# VL6180_2.net
KiCad netlist of a schematic drawn in EAGLE
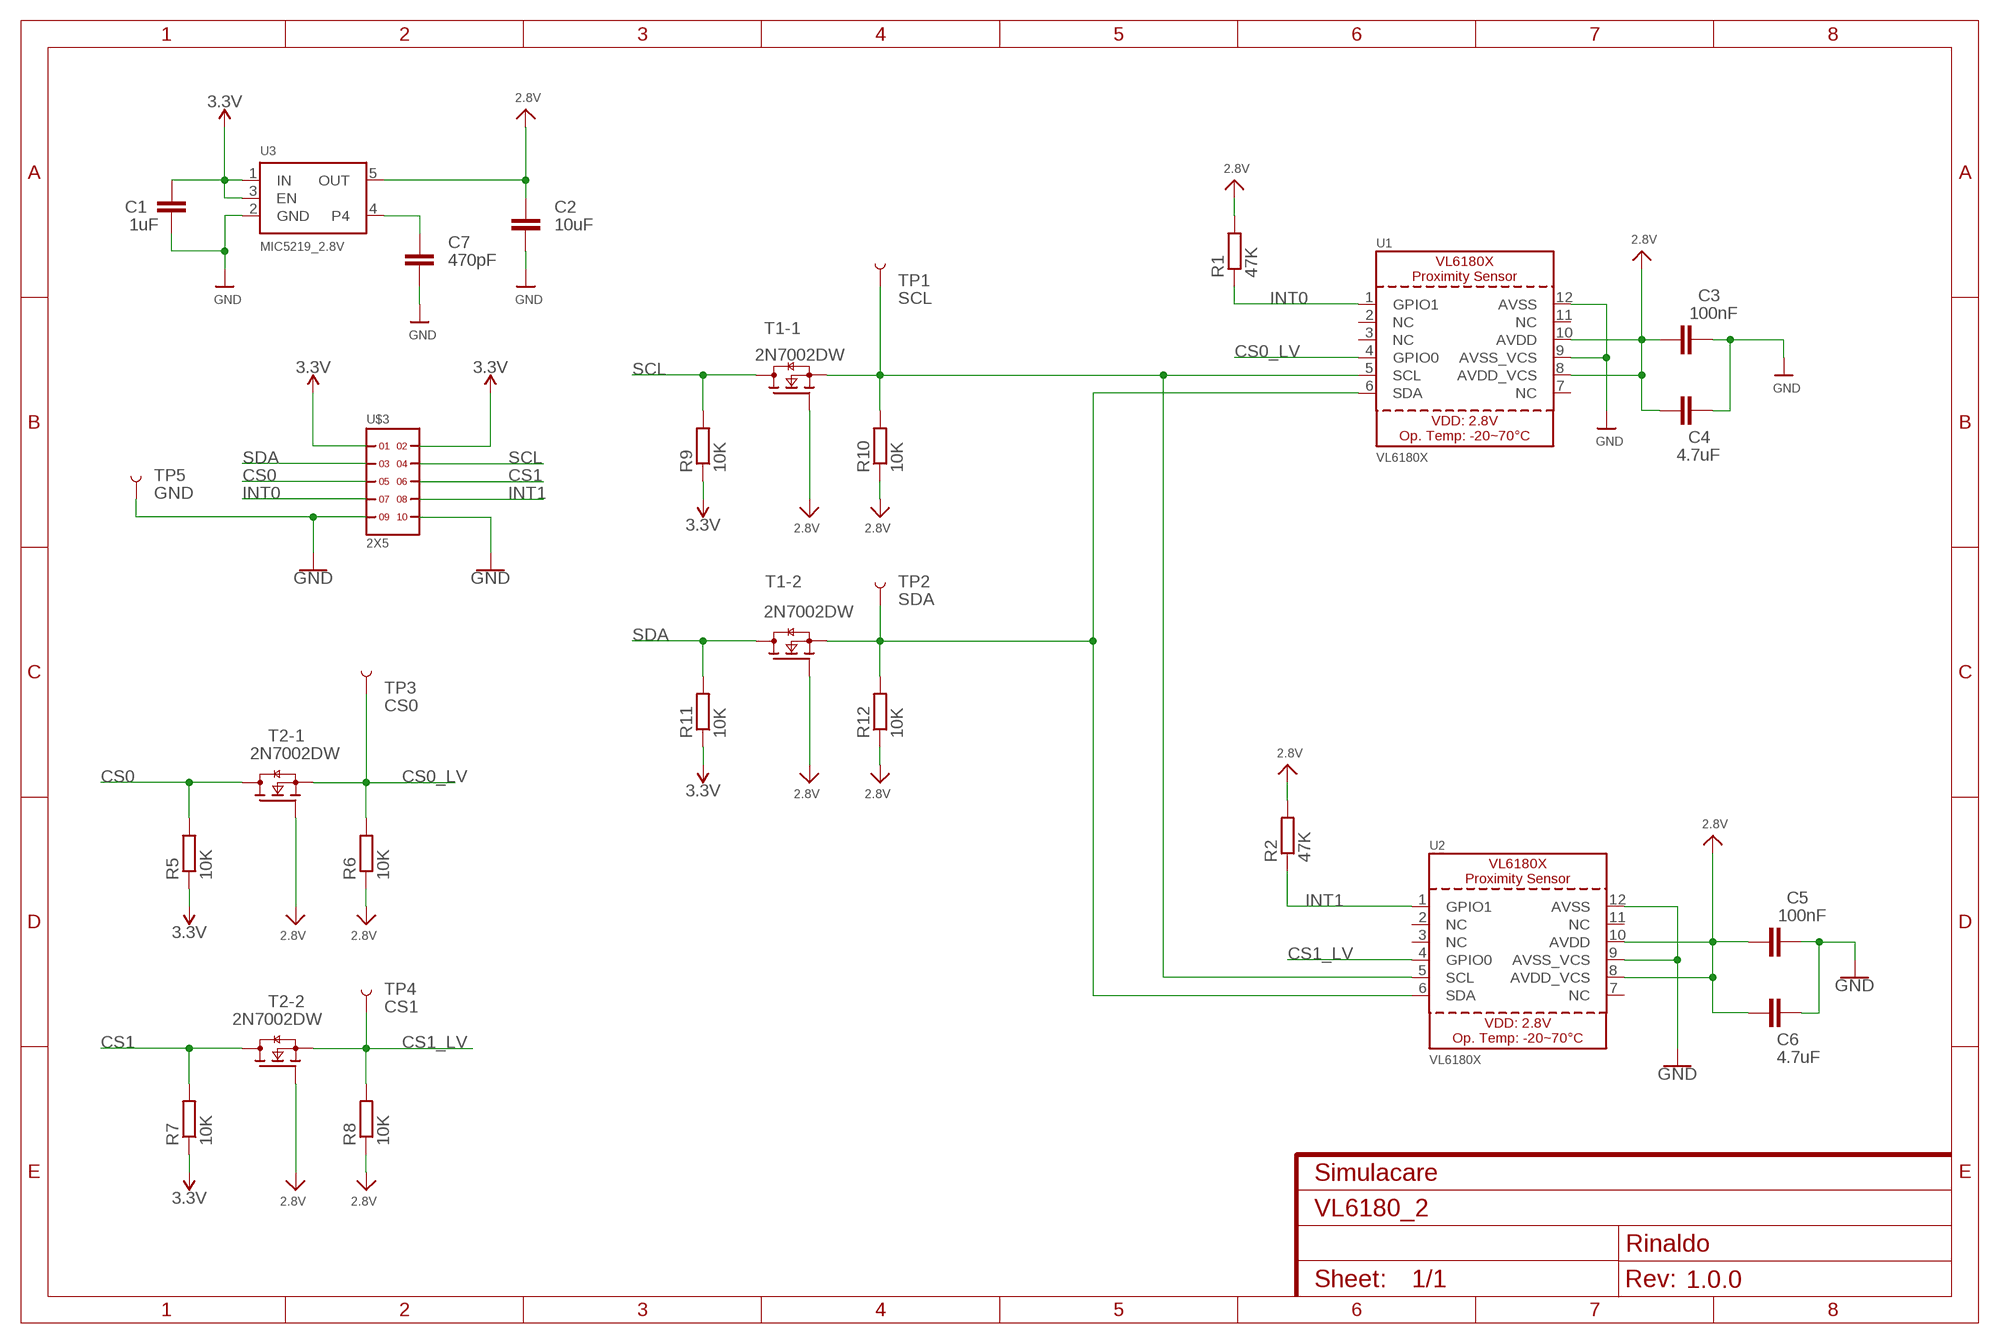
[diagram p0: schematic, sheet 1]

(export (version "E")
  (design (tool "Eeschema 10.0.6"))
  (components
    (comp (ref "C1")
      (value "1uF")
      (footprint "eagle-import:C0603")
      (libsource (lib "eagle-import") (part "C-EUC0603"))
    )
    (comp (ref "C2")
      (value "10uF")
      (footprint "eagle-import:C0603")
      (libsource (lib "eagle-import") (part "C-EUC0603"))
    )
    (comp (ref "C3")
      (value "100nF")
      (footprint "eagle-import:C0603")
      (libsource (lib "eagle-import") (part "C-EUC0603"))
    )
    (comp (ref "C4")
      (value "4.7uF")
      (footprint "eagle-import:C0603")
      (libsource (lib "eagle-import") (part "C-EUC0603"))
    )
    (comp (ref "C5")
      (value "100nF")
      (footprint "eagle-import:C0603")
      (libsource (lib "eagle-import") (part "C-EUC0603"))
    )
    (comp (ref "C6")
      (value "4.7uF")
      (footprint "eagle-import:C0603")
      (libsource (lib "eagle-import") (part "C-EUC0603"))
    )
    (comp (ref "C7")
      (value "470pF")
      (footprint "eagle-import:C0603")
      (libsource (lib "eagle-import") (part "C-EUC0603"))
    )
    (comp (ref "R1")
      (value "47K")
      (footprint "eagle-import:R0603")
      (libsource (lib "eagle-import") (part "R-EU_R0603"))
    )
    (comp (ref "R2")
      (value "47K")
      (footprint "eagle-import:R0603")
      (libsource (lib "eagle-import") (part "R-EU_R0603"))
    )
    (comp (ref "R5")
      (value "10K")
      (footprint "eagle-import:R0603")
      (libsource (lib "eagle-import") (part "R-EU_R0603"))
    )
    (comp (ref "R6")
      (value "10K")
      (footprint "eagle-import:R0603")
      (libsource (lib "eagle-import") (part "R-EU_R0603"))
    )
    (comp (ref "R7")
      (value "10K")
      (footprint "eagle-import:R0603")
      (libsource (lib "eagle-import") (part "R-EU_R0603"))
    )
    (comp (ref "R8")
      (value "10K")
      (footprint "eagle-import:R0603")
      (libsource (lib "eagle-import") (part "R-EU_R0603"))
    )
    (comp (ref "R9")
      (value "10K")
      (footprint "eagle-import:R0603")
      (libsource (lib "eagle-import") (part "R-EU_R0603"))
    )
    (comp (ref "R10")
      (value "10K")
      (footprint "eagle-import:R0603")
      (libsource (lib "eagle-import") (part "R-EU_R0603"))
    )
    (comp (ref "R11")
      (value "10K")
      (footprint "eagle-import:R0603")
      (libsource (lib "eagle-import") (part "R-EU_R0603"))
    )
    (comp (ref "R12")
      (value "10K")
      (footprint "eagle-import:R0603")
      (libsource (lib "eagle-import") (part "R-EU_R0603"))
    )
    (comp (ref "T1")
      (value "2N7002DW")
      (footprint "eagle-import:SOT363")
      (libsource (lib "eagle-import") (part "2N7002BKS"))
    )
    (comp (ref "T2")
      (value "2N7002DW")
      (footprint "eagle-import:SOT363")
      (libsource (lib "eagle-import") (part "2N7002BKS"))
    )
    (comp (ref "TP1")
      (value "SCL")
      (footprint "eagle-import:PAD.03X.04")
      (libsource (lib "eagle-import") (part "TEST-POINT3X4"))
    )
    (comp (ref "TP2")
      (value "SDA")
      (footprint "eagle-import:PAD.03X.04")
      (libsource (lib "eagle-import") (part "TEST-POINT3X4"))
    )
    (comp (ref "TP3")
      (value "CS0")
      (footprint "eagle-import:PAD.03X.04")
      (libsource (lib "eagle-import") (part "TEST-POINT3X4"))
    )
    (comp (ref "TP4")
      (value "CS1")
      (footprint "eagle-import:PAD.03X.04")
      (libsource (lib "eagle-import") (part "TEST-POINT3X4"))
    )
    (comp (ref "TP5")
      (value "GND")
      (footprint "eagle-import:PAD.03X.04")
      (libsource (lib "eagle-import") (part "TEST-POINT3X4"))
    )
    (comp (ref "U$3")
      (value "2X5")
      (footprint "eagle-import:2X5")
      (libsource (lib "eagle-import") (part "2X5"))
    )
    (comp (ref "U1")
      (value "VL6180X")
      (footprint "eagle-import:VL6180")
      (libsource (lib "eagle-import") (part "VL6180X"))
    )
    (comp (ref "U2")
      (value "VL6180X")
      (footprint "eagle-import:VL6180")
      (libsource (lib "eagle-import") (part "VL6180X"))
    )
    (comp (ref "U3")
      (value "MIC5219_2.8V")
      (footprint "eagle-import:SOT23-5")
      (libsource (lib "eagle-import") (part "VREG_SOT23-5"))
    )
  )
  (nets
    (net (code "1") (name "/CS0") (class "Default")
      (node (ref "R5") (pin "2") (pinfunction "2_2") (pintype "passive"))
      (node (ref "T2") (pin "6") (pinfunction "D_6") (pintype "passive"))
      (node (ref "U$3") (pin "5") (pinfunction "5_5") (pintype "bidirectional"))
    )
    (net (code "2") (name "/CS0_LV") (class "Default")
      (node (ref "R6") (pin "2") (pinfunction "2_2") (pintype "passive"))
      (node (ref "T2") (pin "1") (pinfunction "S_1") (pintype "passive"))
      (node (ref "TP3") (pin "P$1") (pinfunction "1_P$1") (pintype "bidirectional"))
      (node (ref "U1") (pin "4") (pinfunction "GPIO0_4") (pintype "bidirectional"))
    )
    (net (code "3") (name "/CS1") (class "Default")
      (node (ref "R7") (pin "2") (pinfunction "2_2") (pintype "passive"))
      (node (ref "T2") (pin "3") (pinfunction "D_3") (pintype "passive"))
      (node (ref "U$3") (pin "6") (pinfunction "6_6") (pintype "bidirectional"))
    )
    (net (code "4") (name "/CS1_LV") (class "Default")
      (node (ref "R8") (pin "2") (pinfunction "2_2") (pintype "passive"))
      (node (ref "T2") (pin "4") (pinfunction "S_4") (pintype "passive"))
      (node (ref "TP4") (pin "P$1") (pinfunction "1_P$1") (pintype "bidirectional"))
      (node (ref "U2") (pin "4") (pinfunction "GPIO0_4") (pintype "bidirectional"))
    )
    (net (code "5") (name "/INT0") (class "Default")
      (node (ref "R1") (pin "1") (pinfunction "1_1") (pintype "passive"))
      (node (ref "U$3") (pin "7") (pinfunction "7_7") (pintype "bidirectional"))
      (node (ref "U1") (pin "1") (pinfunction "GPIO1_1") (pintype "bidirectional"))
    )
    (net (code "6") (name "/INT1") (class "Default")
      (node (ref "R2") (pin "1") (pinfunction "1_1") (pintype "passive"))
      (node (ref "U$3") (pin "8") (pinfunction "8_8") (pintype "bidirectional"))
      (node (ref "U2") (pin "1") (pinfunction "GPIO1_1") (pintype "bidirectional"))
    )
    (net (code "7") (name "/SCL") (class "Default")
      (node (ref "R9") (pin "2") (pinfunction "2_2") (pintype "passive"))
      (node (ref "T1") (pin "6") (pinfunction "D_6") (pintype "passive"))
      (node (ref "U$3") (pin "4") (pinfunction "4_4") (pintype "bidirectional"))
    )
    (net (code "8") (name "/SDA") (class "Default")
      (node (ref "R11") (pin "2") (pinfunction "2_2") (pintype "passive"))
      (node (ref "T1") (pin "3") (pinfunction "D_3") (pintype "passive"))
      (node (ref "U$3") (pin "3") (pinfunction "3_3") (pintype "bidirectional"))
    )
    (net (code "9") (name "2.8V") (class "Default")
      (node (ref "C2") (pin "1") (pinfunction "1_1") (pintype "passive"))
      (node (ref "C3") (pin "1") (pinfunction "1_1") (pintype "passive"))
      (node (ref "C4") (pin "1") (pinfunction "1_1") (pintype "passive"))
      (node (ref "C5") (pin "1") (pinfunction "1_1") (pintype "passive"))
      (node (ref "C6") (pin "1") (pinfunction "1_1") (pintype "passive"))
      (node (ref "R1") (pin "2") (pinfunction "2_2") (pintype "passive"))
      (node (ref "R10") (pin "1") (pinfunction "1_1") (pintype "passive"))
      (node (ref "R12") (pin "1") (pinfunction "1_1") (pintype "passive"))
      (node (ref "R2") (pin "2") (pinfunction "2_2") (pintype "passive"))
      (node (ref "R6") (pin "1") (pinfunction "1_1") (pintype "passive"))
      (node (ref "R8") (pin "1") (pinfunction "1_1") (pintype "passive"))
      (node (ref "T1") (pin "2") (pinfunction "G_2") (pintype "passive"))
      (node (ref "T1") (pin "5") (pinfunction "G_5") (pintype "passive"))
      (node (ref "T2") (pin "2") (pinfunction "G_2") (pintype "passive"))
      (node (ref "T2") (pin "5") (pinfunction "G_5") (pintype "passive"))
      (node (ref "U1") (pin "10") (pinfunction "AVDD_10") (pintype "power_in"))
      (node (ref "U1") (pin "8") (pinfunction "AVDD_VCS_8") (pintype "power_in"))
      (node (ref "U2") (pin "10") (pinfunction "AVDD_10") (pintype "power_in"))
      (node (ref "U2") (pin "8") (pinfunction "AVDD_VCS_8") (pintype "power_in"))
      (node (ref "U3") (pin "5") (pinfunction "OUT_5") (pintype "power_in"))
    )
    (net (code "10") (name "3.3V") (class "Default")
      (node (ref "C1") (pin "1") (pinfunction "1_1") (pintype "passive"))
      (node (ref "R11") (pin "1") (pinfunction "1_1") (pintype "passive"))
      (node (ref "R5") (pin "1") (pinfunction "1_1") (pintype "passive"))
      (node (ref "R7") (pin "1") (pinfunction "1_1") (pintype "passive"))
      (node (ref "R9") (pin "1") (pinfunction "1_1") (pintype "passive"))
      (node (ref "U$3") (pin "1") (pinfunction "1_1") (pintype "bidirectional"))
      (node (ref "U$3") (pin "2") (pinfunction "2_2") (pintype "bidirectional"))
      (node (ref "U3") (pin "1") (pinfunction "IN_1") (pintype "power_in"))
      (node (ref "U3") (pin "3") (pinfunction "EN_3") (pintype "input"))
    )
    (net (code "11") (name "GND") (class "Default")
      (node (ref "C1") (pin "2") (pinfunction "2_2") (pintype "passive"))
      (node (ref "C2") (pin "2") (pinfunction "2_2") (pintype "passive"))
      (node (ref "C3") (pin "2") (pinfunction "2_2") (pintype "passive"))
      (node (ref "C4") (pin "2") (pinfunction "2_2") (pintype "passive"))
      (node (ref "C5") (pin "2") (pinfunction "2_2") (pintype "passive"))
      (node (ref "C6") (pin "2") (pinfunction "2_2") (pintype "passive"))
      (node (ref "C7") (pin "2") (pinfunction "2_2") (pintype "passive"))
      (node (ref "TP5") (pin "P$1") (pinfunction "1_P$1") (pintype "bidirectional"))
      (node (ref "U$3") (pin "10") (pinfunction "10_10") (pintype "bidirectional"))
      (node (ref "U$3") (pin "9") (pinfunction "9_9") (pintype "bidirectional"))
      (node (ref "U1") (pin "12") (pinfunction "AVSS_12") (pintype "power_in"))
      (node (ref "U1") (pin "9") (pinfunction "AVSS_VCS_9") (pintype "power_in"))
      (node (ref "U2") (pin "12") (pinfunction "AVSS_12") (pintype "power_in"))
      (node (ref "U2") (pin "9") (pinfunction "AVSS_VCS_9") (pintype "power_in"))
      (node (ref "U3") (pin "2") (pinfunction "GND_2") (pintype "power_in"))
    )
    (net (code "12") (name "Net-(T1A-S)") (class "Default")
      (node (ref "R10") (pin "2") (pinfunction "2_2") (pintype "passive"))
      (node (ref "T1") (pin "1") (pinfunction "S_1") (pintype "passive"))
      (node (ref "TP1") (pin "P$1") (pinfunction "1_P$1") (pintype "bidirectional"))
      (node (ref "U1") (pin "5") (pinfunction "SCL_5") (pintype "input"))
      (node (ref "U2") (pin "5") (pinfunction "SCL_5") (pintype "input"))
    )
    (net (code "13") (name "Net-(T1B-S)") (class "Default")
      (node (ref "R12") (pin "2") (pinfunction "2_2") (pintype "passive"))
      (node (ref "T1") (pin "4") (pinfunction "S_4") (pintype "passive"))
      (node (ref "TP2") (pin "P$1") (pinfunction "1_P$1") (pintype "bidirectional"))
      (node (ref "U1") (pin "6") (pinfunction "SDA_6") (pintype "bidirectional"))
      (node (ref "U2") (pin "6") (pinfunction "SDA_6") (pintype "bidirectional"))
    )
    (net (code "14") (name "Net-(U3-P4)") (class "Default")
      (node (ref "C7") (pin "1") (pinfunction "1_1") (pintype "passive"))
      (node (ref "U3") (pin "4") (pinfunction "P4_4") (pintype "bidirectional"))
    )
    (net (code "15") (name "unconnected-(U1-NC-Pad2)") (class "Default")
      (node (ref "U1") (pin "2") (pinfunction "NC_2") (pintype "no_connect"))
    )
    (net (code "16") (name "unconnected-(U1-NC-Pad3)") (class "Default")
      (node (ref "U1") (pin "3") (pinfunction "NC_3") (pintype "no_connect"))
    )
    (net (code "17") (name "unconnected-(U1-NC-Pad7)") (class "Default")
      (node (ref "U1") (pin "7") (pinfunction "NC_7") (pintype "no_connect"))
    )
    (net (code "18") (name "unconnected-(U1-NC-Pad11)") (class "Default")
      (node (ref "U1") (pin "11") (pinfunction "NC_11") (pintype "no_connect"))
    )
    (net (code "19") (name "unconnected-(U2-NC-Pad2)") (class "Default")
      (node (ref "U2") (pin "2") (pinfunction "NC_2") (pintype "no_connect"))
    )
    (net (code "20") (name "unconnected-(U2-NC-Pad3)") (class "Default")
      (node (ref "U2") (pin "3") (pinfunction "NC_3") (pintype "no_connect"))
    )
    (net (code "21") (name "unconnected-(U2-NC-Pad7)") (class "Default")
      (node (ref "U2") (pin "7") (pinfunction "NC_7") (pintype "no_connect"))
    )
    (net (code "22") (name "unconnected-(U2-NC-Pad11)") (class "Default")
      (node (ref "U2") (pin "11") (pinfunction "NC_11") (pintype "no_connect"))
    )
  )
)
